# gsm.net
KiCad netlist of a schematic drawn in Altium Designer
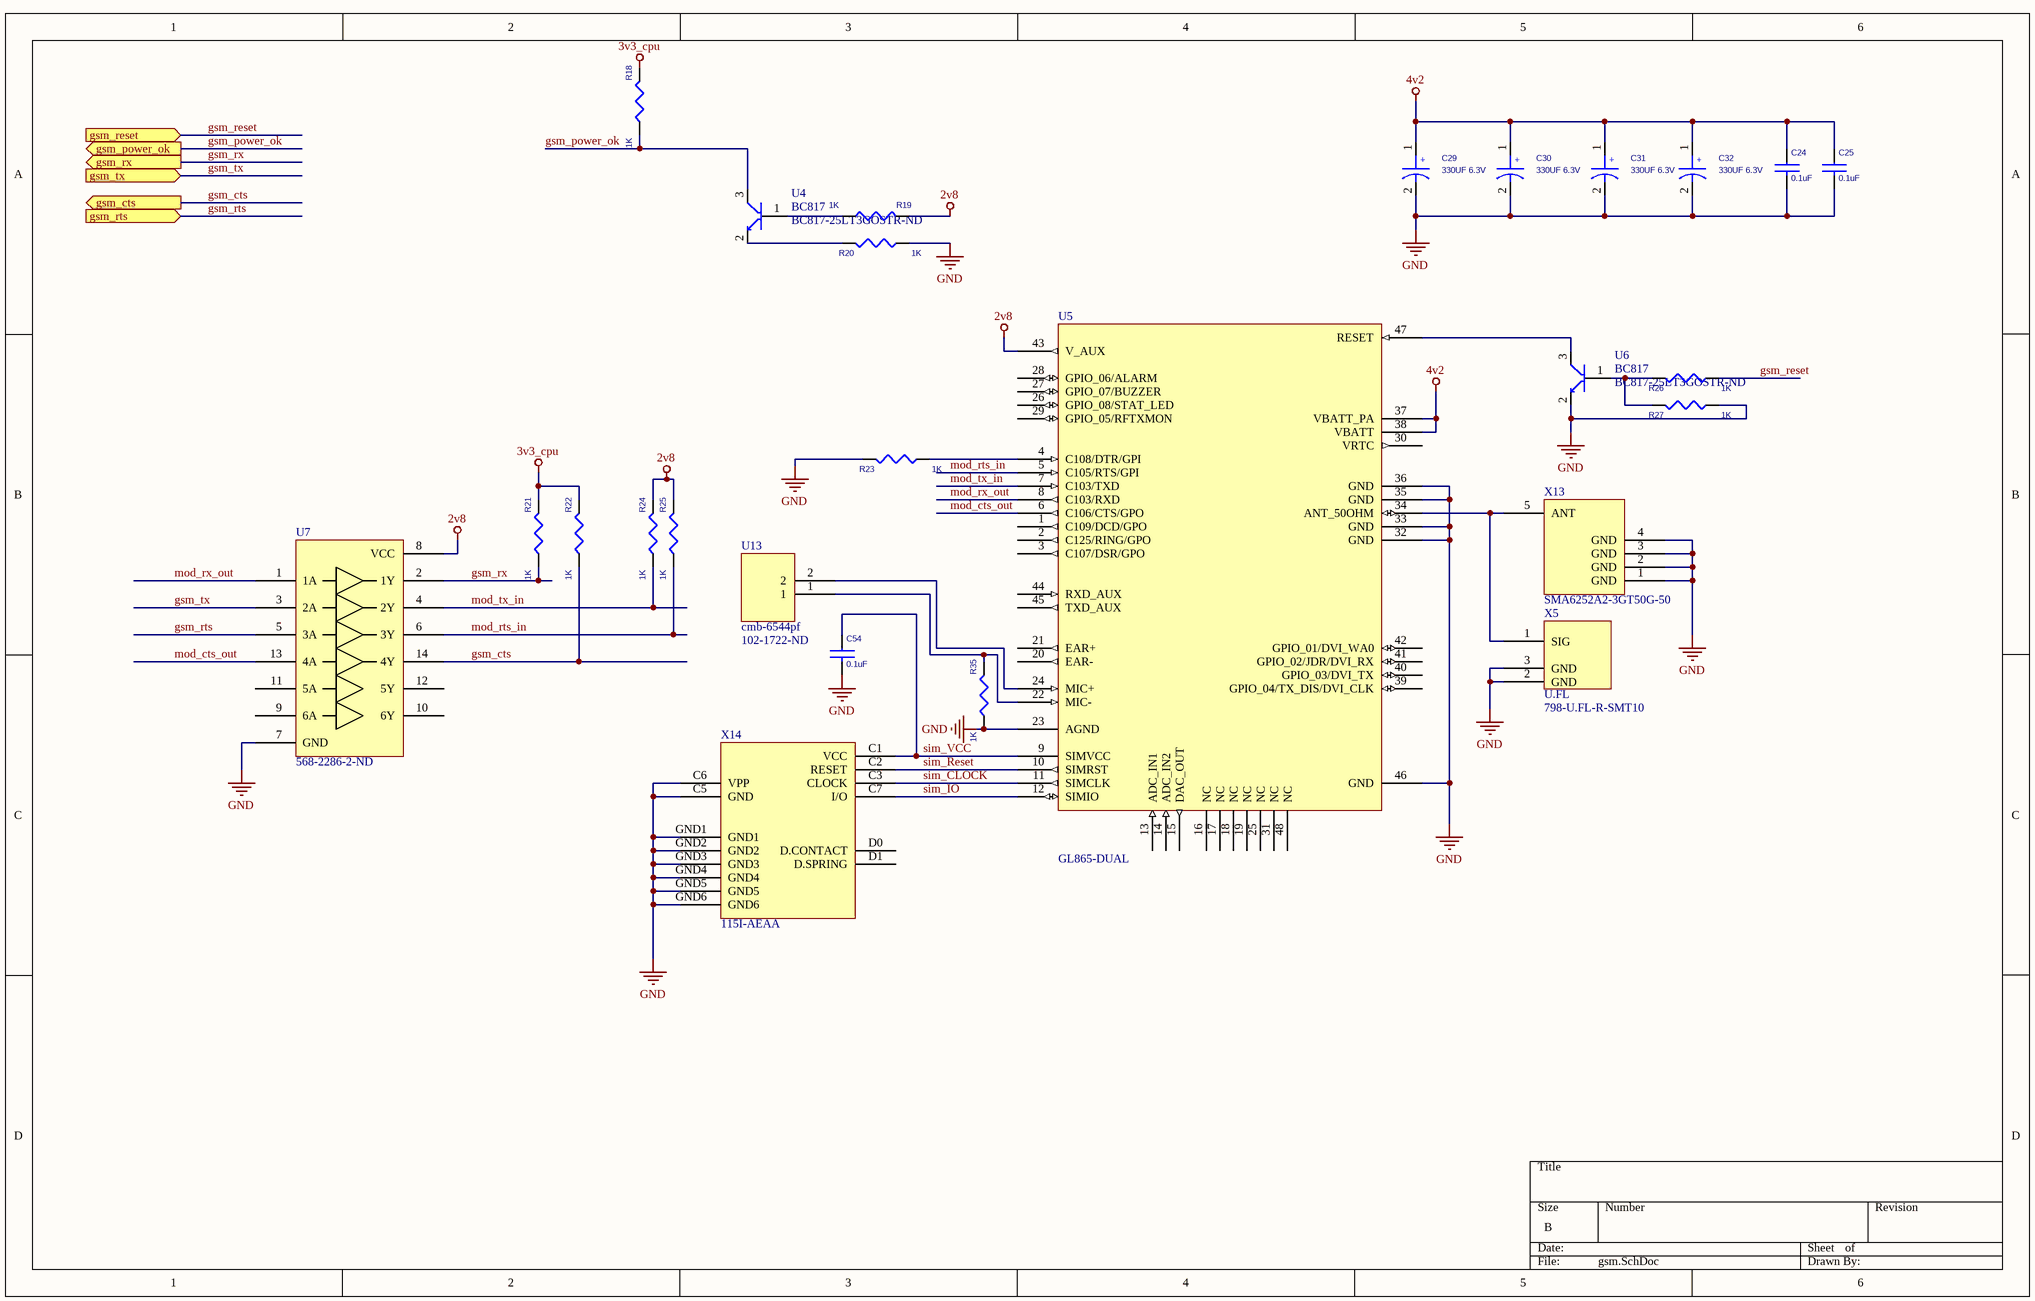
[diagram p0: gsm.SchDoc]

(export (version "E")
  (design (tool "Eeschema 10.0.6"))
  (components
    (comp (ref "C24")
      (value "0.1uF")
      (footprint "CAPC2012X09M")
      (description "CAP CER 0.1UF 25V 10% X7R 0805")
      (libsource (lib "Capacitors") (part "CAP_SMD_0.1UF_10%"))
    )
    (comp (ref "C25")
      (value "0.1uF")
      (footprint "CAPC2012X09M")
      (description "CAP CER 0.1UF 25V 10% X7R 0805")
      (libsource (lib "Capacitors") (part "CAP_SMD_0.1UF_10%"))
    )
    (comp (ref "C29")
      (value "330UF 6.3V")
      (footprint "CAPMP7143X31N")
      (description "CAP 330uF; 6.3V; Case: D")
      (libsource (lib "Capacitors") (part "CAP_SMD_330UF_10%"))
    )
    (comp (ref "C30")
      (value "330UF 6.3V")
      (footprint "CAPMP7143X31N")
      (description "CAP 330uF; 6.3V; Case: D")
      (libsource (lib "Capacitors") (part "CAP_SMD_330UF_10%"))
    )
    (comp (ref "C31")
      (value "330UF 6.3V")
      (footprint "CAPMP7143X31N")
      (description "CAP 330uF; 6.3V; Case: D")
      (libsource (lib "Capacitors") (part "CAP_SMD_330UF_10%"))
    )
    (comp (ref "C32")
      (value "330UF 6.3V")
      (footprint "CAPMP7143X31N")
      (description "CAP 330uF; 6.3V; Case: D")
      (libsource (lib "Capacitors") (part "CAP_SMD_330UF_10%"))
    )
    (comp (ref "C54")
      (value "0.1uF")
      (footprint "CAPC2012X09M")
      (description "CAP CER 0.1UF 25V 10% X7R 0805")
      (libsource (lib "Capacitors") (part "CAP_SMD_0.1UF_10%"))
    )
    (comp (ref "R18")
      (value "1K")
      (footprint "RESC2013X06M")
      (description "RES - 1K OHM, 5%, 1/8W, 0805 SMD")
      (libsource (lib "Resistors") (part "RES_SMD_1K_5%"))
    )
    (comp (ref "R19")
      (value "1K")
      (footprint "RESC2013X06M")
      (description "RES - 1K OHM, 5%, 1/8W, 0805 SMD")
      (libsource (lib "Resistors") (part "RES_SMD_1K_5%"))
    )
    (comp (ref "R20")
      (value "1K")
      (footprint "RESC2013X06M")
      (description "RES - 1K OHM, 5%, 1/8W, 0805 SMD")
      (libsource (lib "Resistors") (part "RES_SMD_1K_5%"))
    )
    (comp (ref "R21")
      (value "1K")
      (footprint "RESC2013X06M")
      (description "RES - 1K OHM, 5%, 1/8W, 0805 SMD")
      (libsource (lib "Resistors") (part "RES_SMD_1K_5%"))
    )
    (comp (ref "R22")
      (value "1K")
      (footprint "RESC2013X06M")
      (description "RES - 1K OHM, 5%, 1/8W, 0805 SMD")
      (libsource (lib "Resistors") (part "RES_SMD_1K_5%"))
    )
    (comp (ref "R23")
      (value "1K")
      (footprint "RESC2013X06M")
      (description "RES - 1K OHM, 5%, 1/8W, 0805 SMD")
      (libsource (lib "Resistors") (part "RES_SMD_1K_5%"))
    )
    (comp (ref "R24")
      (value "1K")
      (footprint "RESC2013X06M")
      (description "RES - 1K OHM, 5%, 1/8W, 0805 SMD")
      (libsource (lib "Resistors") (part "RES_SMD_1K_5%"))
    )
    (comp (ref "R25")
      (value "1K")
      (footprint "RESC2013X06M")
      (description "RES - 1K OHM, 5%, 1/8W, 0805 SMD")
      (libsource (lib "Resistors") (part "RES_SMD_1K_5%"))
    )
    (comp (ref "R26")
      (value "1K")
      (footprint "RESC2013X06M")
      (description "RES - 1K OHM, 5%, 1/8W, 0805 SMD")
      (libsource (lib "Resistors") (part "RES_SMD_1K_5%"))
    )
    (comp (ref "R27")
      (value "1K")
      (footprint "RESC2013X06M")
      (description "RES - 1K OHM, 5%, 1/8W, 0805 SMD")
      (libsource (lib "Resistors") (part "RES_SMD_1K_5%"))
    )
    (comp (ref "R35")
      (value "1K")
      (footprint "RESC2013X06M")
      (description "RES - 1K OHM, 5%, 1/8W, 0805 SMD")
      (libsource (lib "Resistors") (part "RES_SMD_1K_5%"))
    )
    (comp (ref "U4")
      (value "BC817")
      (footprint "SOT95P237X111-3N_SOT-23")
      (fields (field (name "SUPPLIER PART NUMBER 1") "BC817-25LT3GOSTR-ND"))
      (libsource (lib "TruthEar") (part "BC817"))
    )
    (comp (ref "U5")
      (value "GL865-DUAL")
      (footprint "GL865_FOOT")
      (libsource (lib "TruthEar") (part "GL865-DUAL"))
    )
    (comp (ref "U6")
      (value "BC817")
      (footprint "SOT95P237X111-3N_SOT-23")
      (fields (field (name "SUPPLIER PART NUMBER 1") "BC817-25LT3GOSTR-ND"))
      (libsource (lib "TruthEar") (part "BC817"))
    )
    (comp (ref "U7")
      (value "74LVC07A")
      (footprint "TSOP127P600X145-14N")
      (fields (field (name "SUPPLIER PART NUMBER 1") "568-2286-2-ND"))
      (libsource (lib "TruthEar") (part "74LVC07A"))
    )
    (comp (ref "U13")
      (value "cmb-6544pf")
      (footprint "cmb-6544pf")
      (fields (field (name "SUPPLIER PART NUMBER 1") "102-1722-ND"))
      (libsource (lib "TruthEar") (part "cmb-6544pf"))
    )
    (comp (ref "X5")
      (value "U.FL")
      (footprint "U.FL")
      (fields (field (name "SUPPLIER PART NUMBER 1") "798-U.FL-R-SMT10"))
      (libsource (lib "Connectors") (part "U.FL"))
    )
    (comp (ref "X13")
      (value "SMA6252A2-3GT50G-50")
      (footprint "SMA6252A2-3GT50G-50")
      (libsource (lib "Connectors") (part "SMA_CONN"))
    )
    (comp (ref "X14")
      (value "115I-AEAA")
      (footprint "115I-AEAA")
      (libsource (lib "Connectors") (part "SIM_CARD_115I-AEAA"))
    )
  )
  (nets
    (net (code "1") (name "/gsm_cts") (class "Default")
      (node (ref "R22") (pin "1") (pinfunction "1_1") (pintype "passive"))
      (node (ref "U7") (pin "14") (pinfunction "4Y_14") (pintype "power_in"))
    )
    (net (code "2") (name "/gsm_power_ok") (class "Default")
      (node (ref "R18") (pin "1") (pinfunction "1_1") (pintype "passive"))
      (node (ref "U4") (pin "3") (pinfunction "C_3") (pintype "passive"))
    )
    (net (code "3") (name "/gsm_reset") (class "Default")
      (node (ref "R26") (pin "1") (pinfunction "1_1") (pintype "passive"))
    )
    (net (code "4") (name "/gsm_rts") (class "Default")
      (node (ref "U7") (pin "5") (pinfunction "3A_5") (pintype "power_in"))
    )
    (net (code "5") (name "/gsm_rx") (class "Default")
      (node (ref "R21") (pin "1") (pinfunction "1_1") (pintype "passive"))
      (node (ref "U7") (pin "2") (pinfunction "1Y_2") (pintype "power_in"))
    )
    (net (code "6") (name "/gsm_tx") (class "Default")
      (node (ref "U7") (pin "3") (pinfunction "2A_3") (pintype "power_in"))
    )
    (net (code "7") (name "/mod_cts_out") (class "Default")
      (node (ref "U5") (pin "6") (pinfunction "C106/CTS/GPO_6") (pintype "output"))
      (node (ref "U7") (pin "13") (pinfunction "4A_13") (pintype "power_in"))
    )
    (net (code "8") (name "/mod_rts_in") (class "Default")
      (node (ref "R25") (pin "1") (pinfunction "1_1") (pintype "passive"))
      (node (ref "U5") (pin "5") (pinfunction "C105/RTS/GPI_5") (pintype "input"))
      (node (ref "U7") (pin "6") (pinfunction "3Y_6") (pintype "power_in"))
    )
    (net (code "9") (name "/mod_rx_out") (class "Default")
      (node (ref "U5") (pin "8") (pinfunction "C103/RXD_8") (pintype "output"))
      (node (ref "U7") (pin "1") (pinfunction "1A_1") (pintype "power_in"))
    )
    (net (code "10") (name "/mod_tx_in") (class "Default")
      (node (ref "R24") (pin "1") (pinfunction "1_1") (pintype "passive"))
      (node (ref "U5") (pin "7") (pinfunction "C103/TXD_7") (pintype "input"))
      (node (ref "U7") (pin "4") (pinfunction "2Y_4") (pintype "power_in"))
    )
    (net (code "11") (name "/sim_CLOCK") (class "Default")
      (node (ref "U5") (pin "11") (pinfunction "SIMCLK_11") (pintype "output"))
      (node (ref "X14") (pin "C3") (pinfunction "CLOCK_C3") (pintype "passive"))
    )
    (net (code "12") (name "/sim_IO") (class "Default")
      (node (ref "U5") (pin "12") (pinfunction "SIMIO_12") (pintype "bidirectional"))
      (node (ref "X14") (pin "C7") (pinfunction "I/O_C7") (pintype "passive"))
    )
    (net (code "13") (name "/sim_Reset") (class "Default")
      (node (ref "U5") (pin "10") (pinfunction "SIMRST_10") (pintype "output"))
      (node (ref "X14") (pin "C2") (pinfunction "RESET_C2") (pintype "passive"))
    )
    (net (code "14") (name "/sim_VCC") (class "Default")
      (node (ref "C54") (pin "1") (pinfunction "1_1") (pintype "passive"))
      (node (ref "U5") (pin "9") (pinfunction "SIMVCC_9") (pintype "passive"))
      (node (ref "X14") (pin "C1") (pinfunction "VCC_C1") (pintype "passive"))
    )
    (net (code "15") (name "2v8") (class "Default")
      (node (ref "R19") (pin "2") (pinfunction "2_2") (pintype "passive"))
      (node (ref "R24") (pin "2") (pinfunction "2_2") (pintype "passive"))
      (node (ref "R25") (pin "2") (pinfunction "2_2") (pintype "passive"))
      (node (ref "U5") (pin "43") (pinfunction "V_AUX_43") (pintype "output"))
      (node (ref "U7") (pin "8") (pinfunction "VCC_8") (pintype "power_in"))
    )
    (net (code "16") (name "3v3_cpu") (class "Default")
      (node (ref "R18") (pin "2") (pinfunction "2_2") (pintype "passive"))
      (node (ref "R21") (pin "2") (pinfunction "2_2") (pintype "passive"))
      (node (ref "R22") (pin "2") (pinfunction "2_2") (pintype "passive"))
    )
    (net (code "17") (name "4v2") (class "Default")
      (node (ref "C24") (pin "1") (pinfunction "1_1") (pintype "passive"))
      (node (ref "C25") (pin "1") (pinfunction "1_1") (pintype "passive"))
      (node (ref "C29") (pin "1") (pinfunction "1_1") (pintype "passive"))
      (node (ref "C30") (pin "1") (pinfunction "1_1") (pintype "passive"))
      (node (ref "C31") (pin "1") (pinfunction "1_1") (pintype "passive"))
      (node (ref "C32") (pin "1") (pinfunction "1_1") (pintype "passive"))
      (node (ref "U5") (pin "37") (pinfunction "VBATT_PA_37") (pintype "passive"))
      (node (ref "U5") (pin "38") (pinfunction "VBATT_38") (pintype "passive"))
    )
    (net (code "18") (name "GND") (class "Default")
      (node (ref "C24") (pin "2") (pinfunction "2_2") (pintype "passive"))
      (node (ref "C25") (pin "2") (pinfunction "2_2") (pintype "passive"))
      (node (ref "C29") (pin "2") (pinfunction "2_2") (pintype "passive"))
      (node (ref "C30") (pin "2") (pinfunction "2_2") (pintype "passive"))
      (node (ref "C31") (pin "2") (pinfunction "2_2") (pintype "passive"))
      (node (ref "C32") (pin "2") (pinfunction "2_2") (pintype "passive"))
      (node (ref "C54") (pin "2") (pinfunction "2_2") (pintype "passive"))
      (node (ref "R20") (pin "1") (pinfunction "1_1") (pintype "passive"))
      (node (ref "R23") (pin "2") (pinfunction "2_2") (pintype "passive"))
      (node (ref "R27") (pin "1") (pinfunction "1_1") (pintype "passive"))
      (node (ref "R35") (pin "1") (pinfunction "1_1") (pintype "passive"))
      (node (ref "U5") (pin "23") (pinfunction "AGND_23") (pintype "passive"))
      (node (ref "U5") (pin "32") (pinfunction "GND_32") (pintype "passive"))
      (node (ref "U5") (pin "33") (pinfunction "GND_33") (pintype "passive"))
      (node (ref "U5") (pin "35") (pinfunction "GND_35") (pintype "passive"))
      (node (ref "U5") (pin "36") (pinfunction "GND_36") (pintype "passive"))
      (node (ref "U5") (pin "46") (pinfunction "GND_46") (pintype "passive"))
      (node (ref "U6") (pin "2") (pinfunction "E_2") (pintype "passive"))
      (node (ref "U7") (pin "7") (pinfunction "GND_7") (pintype "power_in"))
      (node (ref "X13") (pin "1") (pinfunction "GND_1") (pintype "passive"))
      (node (ref "X13") (pin "2") (pinfunction "GND_2") (pintype "passive"))
      (node (ref "X13") (pin "3") (pinfunction "GND_3") (pintype "passive"))
      (node (ref "X13") (pin "4") (pinfunction "GND_4") (pintype "passive"))
      (node (ref "X14") (pin "C5") (pinfunction "GND_C5") (pintype "passive"))
      (node (ref "X14") (pin "C6") (pinfunction "VPP_C6") (pintype "passive"))
      (node (ref "X14") (pin "GND1") (pinfunction "GND1_GND1") (pintype "passive"))
      (node (ref "X14") (pin "GND2") (pinfunction "GND2_GND2") (pintype "passive"))
      (node (ref "X14") (pin "GND3") (pinfunction "GND3_GND3") (pintype "passive"))
      (node (ref "X14") (pin "GND4") (pinfunction "GND4_GND4") (pintype "passive"))
      (node (ref "X14") (pin "GND5") (pinfunction "GND5_GND5") (pintype "passive"))
      (node (ref "X14") (pin "GND6") (pinfunction "GND6_GND6") (pintype "passive"))
      (node (ref "X5") (pin "2") (pinfunction "GND_2") (pintype "passive"))
      (node (ref "X5") (pin "3") (pinfunction "GND_3") (pintype "passive"))
    )
    (net (code "19") (name "Net-(U4-B)") (class "Default")
      (node (ref "R19") (pin "1") (pinfunction "1_1") (pintype "passive"))
      (node (ref "U4") (pin "1") (pinfunction "B_1") (pintype "passive"))
    )
    (net (code "20") (name "Net-(U4-E)") (class "Default")
      (node (ref "R20") (pin "2") (pinfunction "2_2") (pintype "passive"))
      (node (ref "U4") (pin "2") (pinfunction "E_2") (pintype "passive"))
    )
    (net (code "21") (name "Net-(U5-ANT_50OHM)") (class "Default")
      (node (ref "U5") (pin "34") (pinfunction "ANT_50OHM_34") (pintype "bidirectional"))
      (node (ref "X13") (pin "5") (pinfunction "ANT_5") (pintype "passive"))
      (node (ref "X5") (pin "1") (pinfunction "SIG_1") (pintype "passive"))
    )
    (net (code "22") (name "Net-(U5-C108{slash}DTR{slash}GPI)") (class "Default")
      (node (ref "R23") (pin "1") (pinfunction "1_1") (pintype "passive"))
      (node (ref "U5") (pin "4") (pinfunction "C108/DTR/GPI_4") (pintype "input"))
    )
    (net (code "23") (name "Net-(U5-MIC+)") (class "Default")
      (node (ref "U13") (pin "2") (pinfunction "2_2") (pintype "passive"))
      (node (ref "U5") (pin "24") (pinfunction "MIC+_24") (pintype "input"))
    )
    (net (code "24") (name "Net-(U5-MIC-)") (class "Default")
      (node (ref "R35") (pin "2") (pinfunction "2_2") (pintype "passive"))
      (node (ref "U13") (pin "1") (pinfunction "1_1") (pintype "passive"))
      (node (ref "U5") (pin "22") (pinfunction "MIC-_22") (pintype "input"))
    )
    (net (code "25") (name "Net-(U5-RESET)") (class "Default")
      (node (ref "U5") (pin "47") (pinfunction "RESET_47") (pintype "input"))
      (node (ref "U6") (pin "3") (pinfunction "C_3") (pintype "passive"))
    )
    (net (code "26") (name "Net-(U6-B)") (class "Default")
      (node (ref "R26") (pin "2") (pinfunction "2_2") (pintype "passive"))
      (node (ref "R27") (pin "2") (pinfunction "2_2") (pintype "passive"))
      (node (ref "U6") (pin "1") (pinfunction "B_1") (pintype "passive"))
    )
    (net (code "27") (name "unconnected-(U5-ADC_IN1-Pad13)") (class "Default")
      (node (ref "U5") (pin "13") (pinfunction "ADC_IN1_13") (pintype "input"))
    )
    (net (code "28") (name "unconnected-(U5-ADC_IN2-Pad14)") (class "Default")
      (node (ref "U5") (pin "14") (pinfunction "ADC_IN2_14") (pintype "input"))
    )
    (net (code "29") (name "unconnected-(U5-C107{slash}DSR{slash}GPO-Pad3)") (class "Default")
      (node (ref "U5") (pin "3") (pinfunction "C107/DSR/GPO_3") (pintype "output"))
    )
    (net (code "30") (name "unconnected-(U5-C109{slash}DCD{slash}GPO-Pad1)") (class "Default")
      (node (ref "U5") (pin "1") (pinfunction "C109/DCD/GPO_1") (pintype "output"))
    )
    (net (code "31") (name "unconnected-(U5-C125{slash}RING{slash}GPO-Pad2)") (class "Default")
      (node (ref "U5") (pin "2") (pinfunction "C125/RING/GPO_2") (pintype "output"))
    )
    (net (code "32") (name "unconnected-(U5-DAC_OUT-Pad15)") (class "Default")
      (node (ref "U5") (pin "15") (pinfunction "DAC_OUT_15") (pintype "output"))
    )
    (net (code "33") (name "unconnected-(U5-EAR+-Pad21)") (class "Default")
      (node (ref "U5") (pin "21") (pinfunction "EAR+_21") (pintype "output"))
    )
    (net (code "34") (name "unconnected-(U5-EAR--Pad20)") (class "Default")
      (node (ref "U5") (pin "20") (pinfunction "EAR-_20") (pintype "output"))
    )
    (net (code "35") (name "unconnected-(U5-GPIO_01{slash}DVI_WA0-Pad42)") (class "Default")
      (node (ref "U5") (pin "42") (pinfunction "GPIO_01/DVI_WA0_42") (pintype "bidirectional"))
    )
    (net (code "36") (name "unconnected-(U5-GPIO_02{slash}JDR{slash}DVI_RX-Pad41)") (class "Default")
      (node (ref "U5") (pin "41") (pinfunction "GPIO_02/JDR/DVI_RX_41") (pintype "bidirectional"))
    )
    (net (code "37") (name "unconnected-(U5-GPIO_03{slash}DVI_TX-Pad40)") (class "Default")
      (node (ref "U5") (pin "40") (pinfunction "GPIO_03/DVI_TX_40") (pintype "bidirectional"))
    )
    (net (code "38") (name "unconnected-(U5-GPIO_04{slash}TX_DIS{slash}DVI_CLK-Pad39)") (class "Default")
      (node (ref "U5") (pin "39") (pinfunction "GPIO_04/TX_DIS/DVI_CLK_39") (pintype "bidirectional"))
    )
    (net (code "39") (name "unconnected-(U5-GPIO_05{slash}RFTXMON-Pad29)") (class "Default")
      (node (ref "U5") (pin "29") (pinfunction "GPIO_05/RFTXMON_29") (pintype "bidirectional"))
    )
    (net (code "40") (name "unconnected-(U5-GPIO_06{slash}ALARM-Pad28)") (class "Default")
      (node (ref "U5") (pin "28") (pinfunction "GPIO_06/ALARM_28") (pintype "bidirectional"))
    )
    (net (code "41") (name "unconnected-(U5-GPIO_07{slash}BUZZER-Pad27)") (class "Default")
      (node (ref "U5") (pin "27") (pinfunction "GPIO_07/BUZZER_27") (pintype "bidirectional"))
    )
    (net (code "42") (name "unconnected-(U5-GPIO_08{slash}STAT_LED-Pad26)") (class "Default")
      (node (ref "U5") (pin "26") (pinfunction "GPIO_08/STAT_LED_26") (pintype "bidirectional"))
    )
    (net (code "43") (name "unconnected-(U5-NC-Pad16)") (class "Default")
      (node (ref "U5") (pin "16") (pinfunction "NC_16") (pintype "passive"))
    )
    (net (code "44") (name "unconnected-(U5-NC-Pad17)") (class "Default")
      (node (ref "U5") (pin "17") (pinfunction "NC_17") (pintype "passive"))
    )
    (net (code "45") (name "unconnected-(U5-NC-Pad18)") (class "Default")
      (node (ref "U5") (pin "18") (pinfunction "NC_18") (pintype "passive"))
    )
    (net (code "46") (name "unconnected-(U5-NC-Pad19)") (class "Default")
      (node (ref "U5") (pin "19") (pinfunction "NC_19") (pintype "passive"))
    )
    (net (code "47") (name "unconnected-(U5-NC-Pad25)") (class "Default")
      (node (ref "U5") (pin "25") (pinfunction "NC_25") (pintype "passive"))
    )
    (net (code "48") (name "unconnected-(U5-NC-Pad31)") (class "Default")
      (node (ref "U5") (pin "31") (pinfunction "NC_31") (pintype "passive"))
    )
    (net (code "49") (name "unconnected-(U5-NC-Pad48)") (class "Default")
      (node (ref "U5") (pin "48") (pinfunction "NC_48") (pintype "passive"))
    )
    (net (code "50") (name "unconnected-(U5-RXD_AUX-Pad44)") (class "Default")
      (node (ref "U5") (pin "44") (pinfunction "RXD_AUX_44") (pintype "input"))
    )
    (net (code "51") (name "unconnected-(U5-TXD_AUX-Pad45)") (class "Default")
      (node (ref "U5") (pin "45") (pinfunction "TXD_AUX_45") (pintype "output"))
    )
    (net (code "52") (name "unconnected-(U5-VRTC-Pad30)") (class "Default")
      (node (ref "U5") (pin "30") (pinfunction "VRTC_30") (pintype "output"))
    )
    (net (code "53") (name "unconnected-(U7-5A-Pad11)") (class "Default")
      (node (ref "U7") (pin "11") (pinfunction "5A_11") (pintype "power_in"))
    )
    (net (code "54") (name "unconnected-(U7-5Y-Pad12)") (class "Default")
      (node (ref "U7") (pin "12") (pinfunction "5Y_12") (pintype "power_in"))
    )
    (net (code "55") (name "unconnected-(U7-6A-Pad9)") (class "Default")
      (node (ref "U7") (pin "9") (pinfunction "6A_9") (pintype "power_in"))
    )
    (net (code "56") (name "unconnected-(U7-6Y-Pad10)") (class "Default")
      (node (ref "U7") (pin "10") (pinfunction "6Y_10") (pintype "power_in"))
    )
    (net (code "57") (name "unconnected-(X14-D.CONTACT-PadD0)") (class "Default")
      (node (ref "X14") (pin "D0") (pinfunction "D.CONTACT_D0") (pintype "passive"))
    )
    (net (code "58") (name "unconnected-(X14-D.SPRING-PadD1)") (class "Default")
      (node (ref "X14") (pin "D1") (pinfunction "D.SPRING_D1") (pintype "passive"))
    )
  )
)
